# EngineersThumb.net
KiCad netlist of a schematic drawn in EAGLE
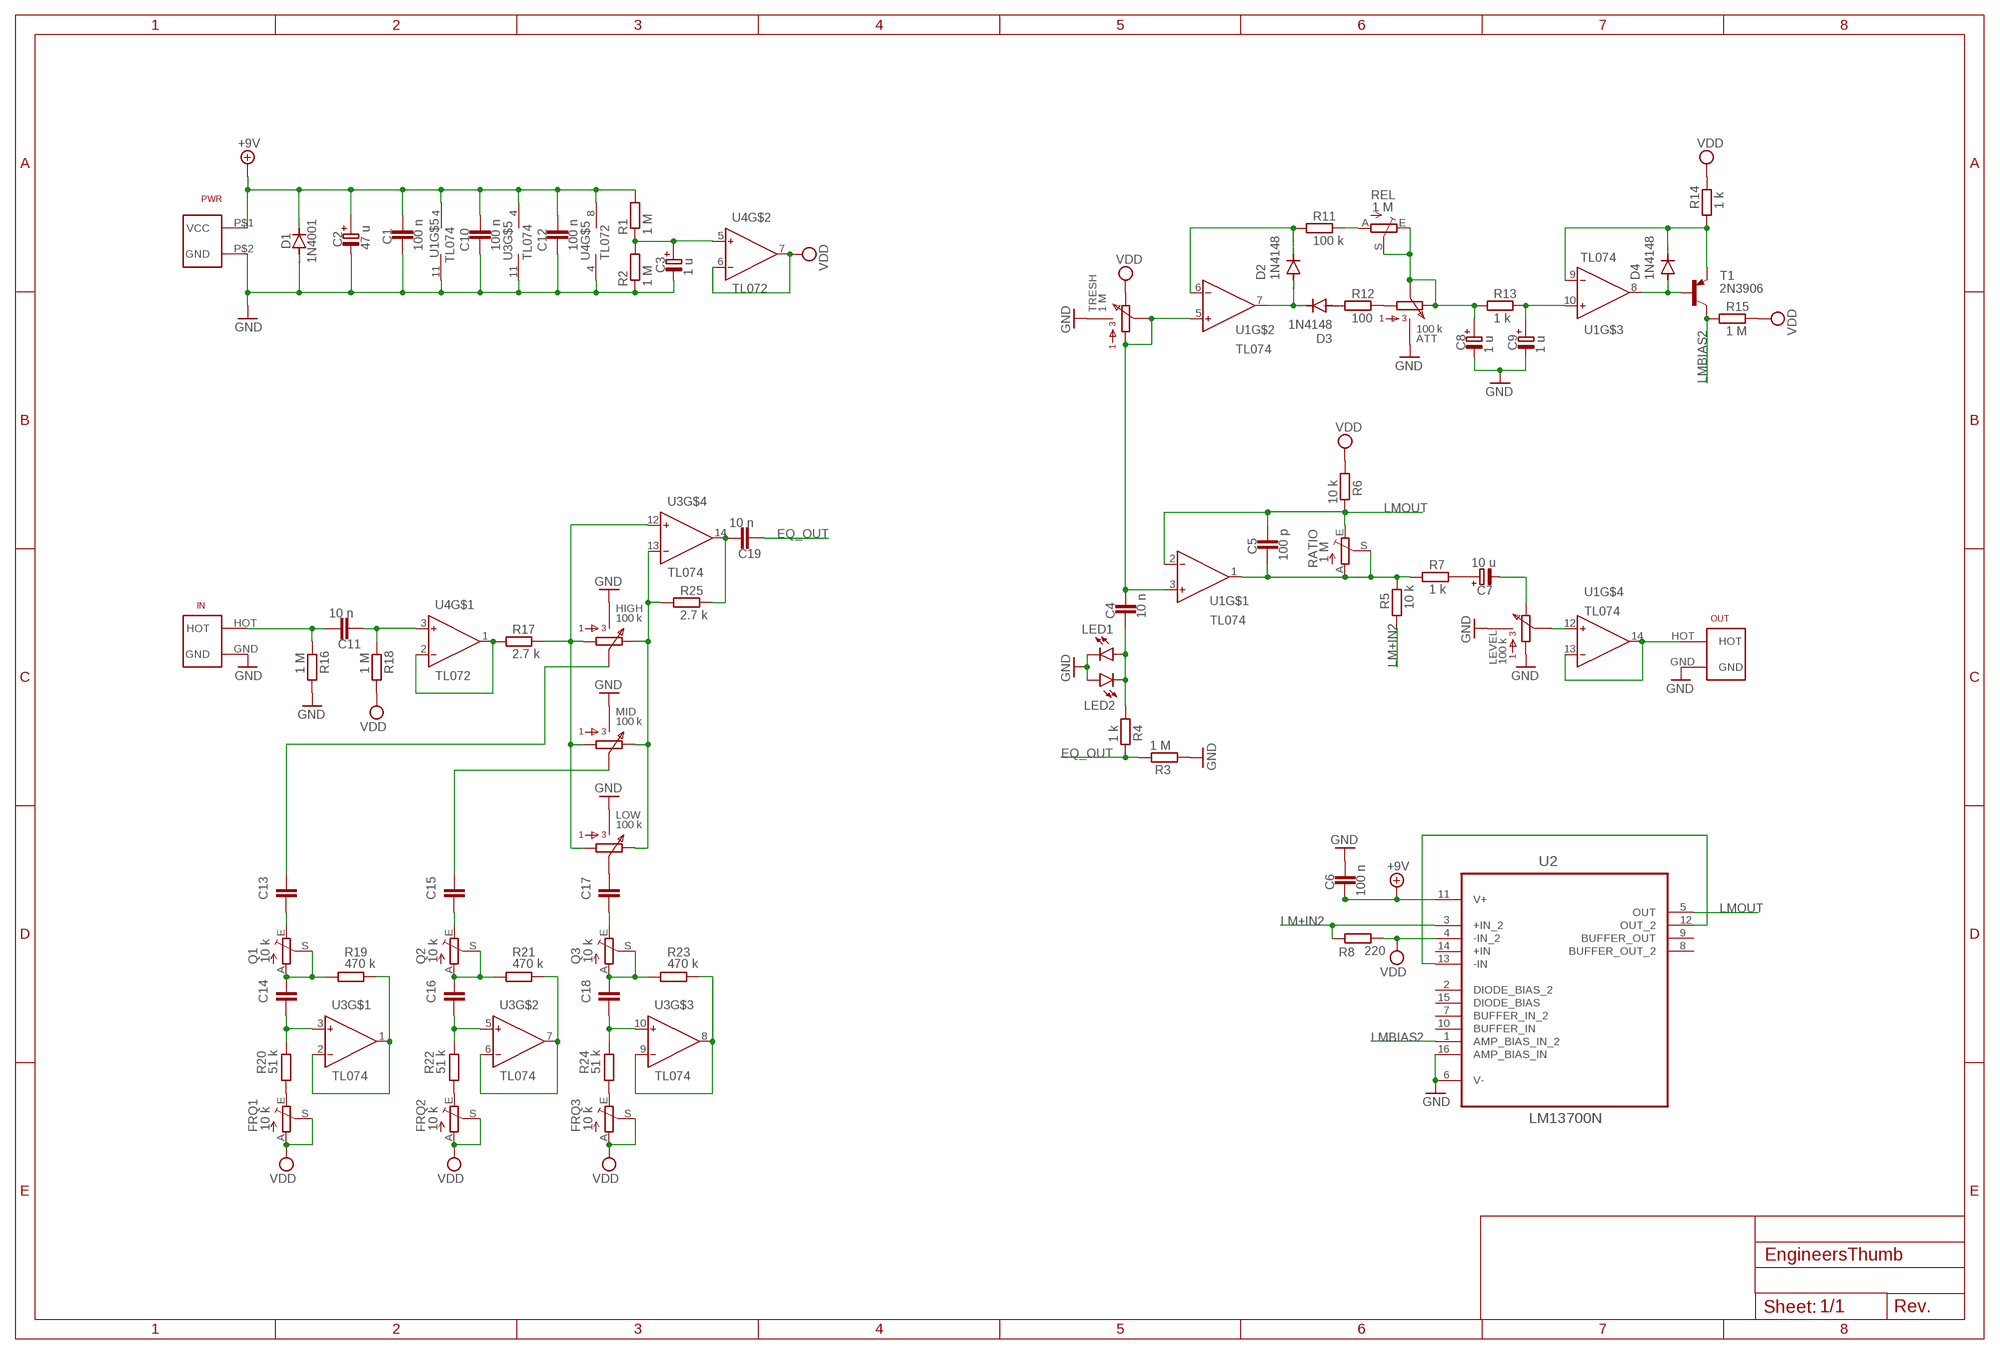
[diagram p0: schematic, sheet 1]

(export (version "E")
  (design (tool "Eeschema 10.0.6"))
  (components
    (comp (ref "ATT")
      (value "100 k")
      (footprint "eagle-import:RK09L1140")
      (libsource (lib "eagle-import") (part "RK09L1140"))
    )
    (comp (ref "C1")
      (value "100 n")
      (footprint "eagle-import:C025-025X050")
      (libsource (lib "eagle-import") (part "C-EU025-025X050"))
    )
    (comp (ref "C2")
      (value "47 u")
      (footprint "eagle-import:E2,0-5")
      (libsource (lib "eagle-import") (part "C-PR-2,0X5"))
    )
    (comp (ref "C3")
      (value "1 u")
      (footprint "eagle-import:E2,0-5")
      (libsource (lib "eagle-import") (part "C-PR-2,0X5"))
    )
    (comp (ref "C4")
      (value "10 n")
      (footprint "eagle-import:C025-025X050")
      (libsource (lib "eagle-import") (part "C-EU025-025X050"))
    )
    (comp (ref "C5")
      (value "100 p")
      (footprint "eagle-import:C025-025X050")
      (libsource (lib "eagle-import") (part "C-EU025-025X050"))
    )
    (comp (ref "C6")
      (value "100 n")
      (footprint "eagle-import:C025-025X050")
      (libsource (lib "eagle-import") (part "C-EU025-025X050"))
    )
    (comp (ref "C7")
      (value "10 u")
      (footprint "eagle-import:E2,0-5")
      (libsource (lib "eagle-import") (part "C-PR-2,0X5"))
    )
    (comp (ref "C8")
      (value "1 u")
      (footprint "eagle-import:E2,0-5")
      (libsource (lib "eagle-import") (part "C-PR-2,0X5"))
    )
    (comp (ref "C9")
      (value "1 u")
      (footprint "eagle-import:E2,0-5")
      (libsource (lib "eagle-import") (part "C-PR-2,0X5"))
    )
    (comp (ref "C10")
      (value "100 n")
      (footprint "eagle-import:C025-025X050")
      (libsource (lib "eagle-import") (part "C-EU025-025X050"))
    )
    (comp (ref "C11")
      (value "10 n")
      (footprint "eagle-import:C025-025X050")
      (libsource (lib "eagle-import") (part "C-EU025-025X050"))
    )
    (comp (ref "C12")
      (value "100 n")
      (footprint "eagle-import:C025-025X050")
      (libsource (lib "eagle-import") (part "C-EU025-025X050"))
    )
    (comp (ref "C13")
      (value "C-EU025-025X050")
      (footprint "eagle-import:C025-025X050")
      (libsource (lib "eagle-import") (part "C-EU025-025X050"))
    )
    (comp (ref "C14")
      (value "C-EU025-025X050")
      (footprint "eagle-import:C025-025X050")
      (libsource (lib "eagle-import") (part "C-EU025-025X050"))
    )
    (comp (ref "C15")
      (value "C-EU025-025X050")
      (footprint "eagle-import:C025-025X050")
      (libsource (lib "eagle-import") (part "C-EU025-025X050"))
    )
    (comp (ref "C16")
      (value "C-EU025-025X050")
      (footprint "eagle-import:C025-025X050")
      (libsource (lib "eagle-import") (part "C-EU025-025X050"))
    )
    (comp (ref "C17")
      (value "C-EU025-025X050")
      (footprint "eagle-import:C025-025X050")
      (libsource (lib "eagle-import") (part "C-EU025-025X050"))
    )
    (comp (ref "C18")
      (value "C-EU025-025X050")
      (footprint "eagle-import:C025-025X050")
      (libsource (lib "eagle-import") (part "C-EU025-025X050"))
    )
    (comp (ref "C19")
      (value "10 n")
      (footprint "eagle-import:C025-025X050")
      (libsource (lib "eagle-import") (part "C-EU025-025X050"))
    )
    (comp (ref "D1")
      (value "1N4001")
      (footprint "eagle-import:DO41-10")
      (libsource (lib "eagle-import") (part "1N4004"))
    )
    (comp (ref "D2")
      (value "1N4148")
      (footprint "eagle-import:DO35-10")
      (libsource (lib "eagle-import") (part "1N4148DO35-10"))
    )
    (comp (ref "D3")
      (value "1N4148")
      (footprint "eagle-import:DO35-10")
      (libsource (lib "eagle-import") (part "1N4148DO35-10"))
    )
    (comp (ref "D4")
      (value "1N4148")
      (footprint "eagle-import:DO35-10")
      (libsource (lib "eagle-import") (part "1N4148DO35-10"))
    )
    (comp (ref "FRQ1")
      (value "10 k")
      (footprint "eagle-import:B64Y")
      (libsource (lib "eagle-import") (part "TRIM_EU-B64Y"))
    )
    (comp (ref "FRQ2")
      (value "10 k")
      (footprint "eagle-import:B64Y")
      (libsource (lib "eagle-import") (part "TRIM_EU-B64Y"))
    )
    (comp (ref "FRQ3")
      (value "10 k")
      (footprint "eagle-import:B64Y")
      (libsource (lib "eagle-import") (part "TRIM_EU-B64Y"))
    )
    (comp (ref "HIGH")
      (value "100 k")
      (footprint "eagle-import:RK09L1140")
      (libsource (lib "eagle-import") (part "RK09L1140"))
    )
    (comp (ref "IN")
      (value "UNBALANCED_INPUT_JACK")
      (footprint "eagle-import:BALANCED_INPUT_JACK")
      (libsource (lib "eagle-import") (part "UNBALANCED_INPUT_JACK"))
    )
    (comp (ref "LED1")
      (value "TLLG4400")
      (footprint "eagle-import:LED3MM")
      (fields (field (name "MF") "VISHAY SEMICONDUCTOR"))
      (libsource (lib "eagle-import") (part "TLLG4400"))
    )
    (comp (ref "LED2")
      (value "TLLG4400")
      (footprint "eagle-import:LED3MM")
      (fields (field (name "MF") "VISHAY SEMICONDUCTOR"))
      (libsource (lib "eagle-import") (part "TLLG4400"))
    )
    (comp (ref "LEVEL")
      (value "100 k")
      (footprint "eagle-import:RK09L1140")
      (libsource (lib "eagle-import") (part "RK09L1140"))
    )
    (comp (ref "LOW")
      (value "100 k")
      (footprint "eagle-import:RK09L1140")
      (libsource (lib "eagle-import") (part "RK09L1140"))
    )
    (comp (ref "MID")
      (value "100 k")
      (footprint "eagle-import:RK09L1140")
      (libsource (lib "eagle-import") (part "RK09L1140"))
    )
    (comp (ref "OUT")
      (value "UNBALANCED_INPUT_JACK")
      (footprint "eagle-import:BALANCED_INPUT_JACK")
      (libsource (lib "eagle-import") (part "UNBALANCED_INPUT_JACK"))
    )
    (comp (ref "PWR")
      (value "PWR")
      (footprint "eagle-import:PWR")
      (libsource (lib "eagle-import") (part "PWR"))
    )
    (comp (ref "Q1")
      (value "10 k")
      (footprint "eagle-import:B64Y")
      (libsource (lib "eagle-import") (part "TRIM_EU-B64Y"))
    )
    (comp (ref "Q2")
      (value "10 k")
      (footprint "eagle-import:B64Y")
      (libsource (lib "eagle-import") (part "TRIM_EU-B64Y"))
    )
    (comp (ref "Q3")
      (value "10 k")
      (footprint "eagle-import:B64Y")
      (libsource (lib "eagle-import") (part "TRIM_EU-B64Y"))
    )
    (comp (ref "R1")
      (value "1 M")
      (footprint "eagle-import:0204_7")
      (libsource (lib "eagle-import") (part "R-EU_0204/7"))
    )
    (comp (ref "R2")
      (value "1 M")
      (footprint "eagle-import:0204_7")
      (libsource (lib "eagle-import") (part "R-EU_0204/7"))
    )
    (comp (ref "R3")
      (value "1 M")
      (footprint "eagle-import:0204_7")
      (libsource (lib "eagle-import") (part "R-EU_0204/7"))
    )
    (comp (ref "R4")
      (value "1 k")
      (footprint "eagle-import:0204_7")
      (libsource (lib "eagle-import") (part "R-EU_0204/7"))
    )
    (comp (ref "R5")
      (value "10 k")
      (footprint "eagle-import:0204_7")
      (libsource (lib "eagle-import") (part "R-EU_0204/7"))
    )
    (comp (ref "R6")
      (value "10 k")
      (footprint "eagle-import:0204_7")
      (libsource (lib "eagle-import") (part "R-EU_0204/7"))
    )
    (comp (ref "R7")
      (value "1 k")
      (footprint "eagle-import:0204_7")
      (libsource (lib "eagle-import") (part "R-EU_0204/7"))
    )
    (comp (ref "R8")
      (value "220")
      (footprint "eagle-import:0204_7")
      (libsource (lib "eagle-import") (part "R-EU_0204/7"))
    )
    (comp (ref "R11")
      (value "100 k")
      (footprint "eagle-import:0204_7")
      (libsource (lib "eagle-import") (part "R-EU_0204/7"))
    )
    (comp (ref "R12")
      (value "100")
      (footprint "eagle-import:0204_7")
      (libsource (lib "eagle-import") (part "R-EU_0204/7"))
    )
    (comp (ref "R13")
      (value "1 k")
      (footprint "eagle-import:0204_7")
      (libsource (lib "eagle-import") (part "R-EU_0204/7"))
    )
    (comp (ref "R14")
      (value "1 k")
      (footprint "eagle-import:0204_7")
      (libsource (lib "eagle-import") (part "R-EU_0204/7"))
    )
    (comp (ref "R15")
      (value "1 M")
      (footprint "eagle-import:0204_7")
      (libsource (lib "eagle-import") (part "R-EU_0204/7"))
    )
    (comp (ref "R16")
      (value "1 M")
      (footprint "eagle-import:0204_7")
      (libsource (lib "eagle-import") (part "R-EU_0204/7"))
    )
    (comp (ref "R17")
      (value "2.7 k")
      (footprint "eagle-import:0204_7")
      (libsource (lib "eagle-import") (part "R-EU_0204/7"))
    )
    (comp (ref "R18")
      (value "1 M")
      (footprint "eagle-import:0204_7")
      (libsource (lib "eagle-import") (part "R-EU_0204/7"))
    )
    (comp (ref "R19")
      (value "470 k")
      (footprint "eagle-import:0204_7")
      (libsource (lib "eagle-import") (part "R-EU_0204/7"))
    )
    (comp (ref "R20")
      (value "51 k")
      (footprint "eagle-import:0204_7")
      (libsource (lib "eagle-import") (part "R-EU_0204/7"))
    )
    (comp (ref "R21")
      (value "470 k")
      (footprint "eagle-import:0204_7")
      (libsource (lib "eagle-import") (part "R-EU_0204/7"))
    )
    (comp (ref "R22")
      (value "51 k")
      (footprint "eagle-import:0204_7")
      (libsource (lib "eagle-import") (part "R-EU_0204/7"))
    )
    (comp (ref "R23")
      (value "470 k")
      (footprint "eagle-import:0204_7")
      (libsource (lib "eagle-import") (part "R-EU_0204/7"))
    )
    (comp (ref "R24")
      (value "51 k")
      (footprint "eagle-import:0204_7")
      (libsource (lib "eagle-import") (part "R-EU_0204/7"))
    )
    (comp (ref "R25")
      (value "2.7 k")
      (footprint "eagle-import:0204_7")
      (libsource (lib "eagle-import") (part "R-EU_0204/7"))
    )
    (comp (ref "RATIO")
      (value "1 M")
      (footprint "eagle-import:B64Y")
      (libsource (lib "eagle-import") (part "TRIM_EU-B64Y"))
    )
    (comp (ref "REL")
      (value "1 M")
      (footprint "eagle-import:B64Y")
      (libsource (lib "eagle-import") (part "TRIM_EU-B64Y"))
    )
    (comp (ref "T1")
      (value "2N3906")
      (footprint "eagle-import:TO92")
      (libsource (lib "eagle-import") (part "2N3906"))
    )
    (comp (ref "TRESH")
      (value "1 M")
      (footprint "eagle-import:RK09L1140")
      (libsource (lib "eagle-import") (part "RK09L1140"))
    )
    (comp (ref "U1")
      (value "TL074")
      (footprint "eagle-import:DIP762W53P254L1969H508Q14B")
      (fields (field (name "MPN") "TL074CN"))
      (libsource (lib "eagle-import") (part "TL074IDTPDIP-14"))
    )
    (comp (ref "U2")
      (value "LM13700N")
      (footprint "eagle-import:DIP254P762X508-16")
      (fields (field (name "MPN") "LM13700N/NOPB"))
      (libsource (lib "eagle-import") (part "LM13700N"))
    )
    (comp (ref "U3")
      (value "TL074")
      (footprint "eagle-import:DIP762W53P254L1969H508Q14B")
      (fields (field (name "MPN") "TL074CN"))
      (libsource (lib "eagle-import") (part "TL074IDTPDIP-14"))
    )
    (comp (ref "U4")
      (value "TL072")
      (footprint "eagle-import:DIP762W53P254L980H508Q8B")
      (fields (field (name "MPN") "TL072IP"))
      (libsource (lib "eagle-import") (part "TL072PDIP-8"))
    )
  )
  (nets
    (net (code "1") (name "+9V") (class "Default")
      (node (ref "C1") (pin "1") (pinfunction "1_1") (pintype "passive"))
      (node (ref "C10") (pin "1") (pinfunction "1_1") (pintype "passive"))
      (node (ref "C12") (pin "1") (pinfunction "1_1") (pintype "passive"))
      (node (ref "C2") (pin "+") (pinfunction "+_+") (pintype "passive"))
      (node (ref "C6") (pin "2") (pinfunction "2_2") (pintype "passive"))
      (node (ref "D1") (pin "C") (pinfunction "C_C") (pintype "passive"))
      (node (ref "PWR") (pin "P$1") (pinfunction "VCC_P$1") (pintype "bidirectional"))
      (node (ref "R1") (pin "2") (pinfunction "2_2") (pintype "passive"))
      (node (ref "U1") (pin "4") (pinfunction "V+_4") (pintype "power_in"))
      (node (ref "U2") (pin "11") (pinfunction "V+_11") (pintype "power_in"))
      (node (ref "U3") (pin "4") (pinfunction "V+_4") (pintype "power_in"))
      (node (ref "U4") (pin "8") (pinfunction "V+_8") (pintype "power_in"))
    )
    (net (code "2") (name "/EQ_OUT") (class "Default")
      (node (ref "C19") (pin "2") (pinfunction "2_2") (pintype "passive"))
      (node (ref "R3") (pin "2") (pinfunction "2_2") (pintype "passive"))
      (node (ref "R4") (pin "2") (pinfunction "2_2") (pintype "passive"))
    )
    (net (code "3") (name "/LM+IN2") (class "Default")
      (node (ref "R5") (pin "1") (pinfunction "1_1") (pintype "passive"))
      (node (ref "R8") (pin "1") (pinfunction "1_1") (pintype "passive"))
      (node (ref "U2") (pin "3") (pinfunction "+IN_2_3") (pintype "input"))
    )
    (net (code "4") (name "/LMBIAS2") (class "Default")
      (node (ref "R15") (pin "1") (pinfunction "1_1") (pintype "passive"))
      (node (ref "T1") (pin "1") (pinfunction "C_1") (pintype "passive"))
      (node (ref "U2") (pin "1") (pinfunction "AMP_BIAS_IN_2_1") (pintype "input"))
    )
    (net (code "5") (name "/LMOUT") (class "Default")
      (node (ref "C5") (pin "1") (pinfunction "1_1") (pintype "passive"))
      (node (ref "R6") (pin "2") (pinfunction "2_2") (pintype "passive"))
      (node (ref "RATIO") (pin "E") (pinfunction "E_E") (pintype "passive"))
      (node (ref "U1") (pin "2") (pinfunction "IN-_2") (pintype "input"))
      (node (ref "U2") (pin "5") (pinfunction "OUT_5") (pintype "output"))
    )
    (net (code "6") (name "GND") (class "Default")
      (node (ref "ATT") (pin "P$4") (pinfunction "P$1_P$4") (pintype "bidirectional"))
      (node (ref "ATT") (pin "P$5") (pinfunction "P$1_P$5") (pintype "bidirectional"))
      (node (ref "C1") (pin "2") (pinfunction "2_2") (pintype "passive"))
      (node (ref "C10") (pin "2") (pinfunction "2_2") (pintype "passive"))
      (node (ref "C12") (pin "2") (pinfunction "2_2") (pintype "passive"))
      (node (ref "C2") (pin "-") (pinfunction "-_-") (pintype "passive"))
      (node (ref "C3") (pin "-") (pinfunction "-_-") (pintype "passive"))
      (node (ref "C6") (pin "1") (pinfunction "1_1") (pintype "passive"))
      (node (ref "C8") (pin "-") (pinfunction "-_-") (pintype "passive"))
      (node (ref "C9") (pin "-") (pinfunction "-_-") (pintype "passive"))
      (node (ref "D1") (pin "A") (pinfunction "A_A") (pintype "passive"))
      (node (ref "HIGH") (pin "P$4") (pinfunction "P$1_P$4") (pintype "bidirectional"))
      (node (ref "HIGH") (pin "P$5") (pinfunction "P$1_P$5") (pintype "bidirectional"))
      (node (ref "IN") (pin "GND") (pinfunction "GND_GND") (pintype "bidirectional"))
      (node (ref "LED1") (pin "K") (pinfunction "C_K") (pintype "passive"))
      (node (ref "LED2") (pin "A") (pinfunction "A_A") (pintype "passive"))
      (node (ref "LEVEL") (pin "P$1") (pinfunction "1_P$1") (pintype "passive"))
      (node (ref "LEVEL") (pin "P$4") (pinfunction "P$1_P$4") (pintype "bidirectional"))
      (node (ref "LEVEL") (pin "P$5") (pinfunction "P$1_P$5") (pintype "bidirectional"))
      (node (ref "LOW") (pin "P$4") (pinfunction "P$1_P$4") (pintype "bidirectional"))
      (node (ref "LOW") (pin "P$5") (pinfunction "P$1_P$5") (pintype "bidirectional"))
      (node (ref "MID") (pin "P$4") (pinfunction "P$1_P$4") (pintype "bidirectional"))
      (node (ref "MID") (pin "P$5") (pinfunction "P$1_P$5") (pintype "bidirectional"))
      (node (ref "OUT") (pin "GND") (pinfunction "GND_GND") (pintype "bidirectional"))
      (node (ref "PWR") (pin "P$2") (pinfunction "GND_P$2") (pintype "bidirectional"))
      (node (ref "R16") (pin "1") (pinfunction "1_1") (pintype "passive"))
      (node (ref "R2") (pin "1") (pinfunction "1_1") (pintype "passive"))
      (node (ref "R3") (pin "1") (pinfunction "1_1") (pintype "passive"))
      (node (ref "TRESH") (pin "P$4") (pinfunction "P$1_P$4") (pintype "bidirectional"))
      (node (ref "TRESH") (pin "P$5") (pinfunction "P$1_P$5") (pintype "bidirectional"))
      (node (ref "U1") (pin "11") (pinfunction "V-_11") (pintype "power_in"))
      (node (ref "U2") (pin "16") (pinfunction "AMP_BIAS_IN_16") (pintype "input"))
      (node (ref "U2") (pin "6") (pinfunction "V-_6") (pintype "power_in"))
      (node (ref "U3") (pin "11") (pinfunction "V-_11") (pintype "power_in"))
      (node (ref "U4") (pin "4") (pinfunction "V-_4") (pintype "power_in"))
    )
    (net (code "7") (name "Net-(ATT-1)") (class "Default")
      (node (ref "ATT") (pin "P$1") (pinfunction "1_P$1") (pintype "passive"))
      (node (ref "R12") (pin "2") (pinfunction "2_2") (pintype "passive"))
    )
    (net (code "8") (name "Net-(ATT-2)") (class "Default")
      (node (ref "ATT") (pin "P$2") (pinfunction "2_P$2") (pintype "passive"))
      (node (ref "ATT") (pin "P$3") (pinfunction "3_P$3") (pintype "passive"))
      (node (ref "C8") (pin "+") (pinfunction "+_+") (pintype "passive"))
      (node (ref "R13") (pin "1") (pinfunction "1_1") (pintype "passive"))
      (node (ref "REL") (pin "E") (pinfunction "E_E") (pintype "passive"))
      (node (ref "REL") (pin "S") (pinfunction "S_S") (pintype "passive"))
    )
    (net (code "9") (name "Net-(C7-Pad+)") (class "Default")
      (node (ref "C7") (pin "+") (pinfunction "+_+") (pintype "passive"))
      (node (ref "R7") (pin "2") (pinfunction "2_2") (pintype "passive"))
    )
    (net (code "10") (name "Net-(C11-Pad1)") (class "Default")
      (node (ref "C11") (pin "1") (pinfunction "1_1") (pintype "passive"))
      (node (ref "IN") (pin "HOT") (pinfunction "HOT_HOT") (pintype "bidirectional"))
      (node (ref "R16") (pin "2") (pinfunction "2_2") (pintype "passive"))
    )
    (net (code "11") (name "Net-(C13-Pad1)") (class "Default")
      (node (ref "C13") (pin "1") (pinfunction "1_1") (pintype "passive"))
      (node (ref "Q1") (pin "E") (pinfunction "E_E") (pintype "passive"))
    )
    (net (code "12") (name "Net-(C14-Pad2)") (class "Default")
      (node (ref "C14") (pin "2") (pinfunction "2_2") (pintype "passive"))
      (node (ref "Q1") (pin "A") (pinfunction "A_A") (pintype "passive"))
      (node (ref "Q1") (pin "S") (pinfunction "S_S") (pintype "passive"))
      (node (ref "R19") (pin "1") (pinfunction "1_1") (pintype "passive"))
    )
    (net (code "13") (name "Net-(C15-Pad1)") (class "Default")
      (node (ref "C15") (pin "1") (pinfunction "1_1") (pintype "passive"))
      (node (ref "Q2") (pin "E") (pinfunction "E_E") (pintype "passive"))
    )
    (net (code "14") (name "Net-(C16-Pad2)") (class "Default")
      (node (ref "C16") (pin "2") (pinfunction "2_2") (pintype "passive"))
      (node (ref "Q2") (pin "A") (pinfunction "A_A") (pintype "passive"))
      (node (ref "Q2") (pin "S") (pinfunction "S_S") (pintype "passive"))
      (node (ref "R21") (pin "1") (pinfunction "1_1") (pintype "passive"))
    )
    (net (code "15") (name "Net-(C17-Pad1)") (class "Default")
      (node (ref "C17") (pin "1") (pinfunction "1_1") (pintype "passive"))
      (node (ref "Q3") (pin "E") (pinfunction "E_E") (pintype "passive"))
    )
    (net (code "16") (name "Net-(C18-Pad2)") (class "Default")
      (node (ref "C18") (pin "2") (pinfunction "2_2") (pintype "passive"))
      (node (ref "Q3") (pin "A") (pinfunction "A_A") (pintype "passive"))
      (node (ref "Q3") (pin "S") (pinfunction "S_S") (pintype "passive"))
      (node (ref "R23") (pin "1") (pinfunction "1_1") (pintype "passive"))
    )
    (net (code "17") (name "Net-(D3-PadA)") (class "Default")
      (node (ref "D3") (pin "A") (pinfunction "A_A") (pintype "passive"))
      (node (ref "R12") (pin "1") (pinfunction "1_1") (pintype "passive"))
    )
    (net (code "18") (name "Net-(FRQ1-PadE)") (class "Default")
      (node (ref "FRQ1") (pin "E") (pinfunction "E_E") (pintype "passive"))
      (node (ref "R20") (pin "1") (pinfunction "1_1") (pintype "passive"))
    )
    (net (code "19") (name "Net-(FRQ2-PadE)") (class "Default")
      (node (ref "FRQ2") (pin "E") (pinfunction "E_E") (pintype "passive"))
      (node (ref "R22") (pin "1") (pinfunction "1_1") (pintype "passive"))
    )
    (net (code "20") (name "Net-(FRQ3-PadE)") (class "Default")
      (node (ref "FRQ3") (pin "E") (pinfunction "E_E") (pintype "passive"))
      (node (ref "R24") (pin "1") (pinfunction "1_1") (pintype "passive"))
    )
    (net (code "21") (name "Net-(HIGH-1)") (class "Default")
      (node (ref "HIGH") (pin "P$1") (pinfunction "1_P$1") (pintype "passive"))
      (node (ref "LOW") (pin "P$1") (pinfunction "1_P$1") (pintype "passive"))
      (node (ref "MID") (pin "P$1") (pinfunction "1_P$1") (pintype "passive"))
      (node (ref "R17") (pin "2") (pinfunction "2_2") (pintype "passive"))
      (node (ref "U3") (pin "12") (pinfunction "IN+_12") (pintype "input"))
    )
    (net (code "22") (name "Net-(HIGH-2)") (class "Default")
      (node (ref "C13") (pin "2") (pinfunction "2_2") (pintype "passive"))
      (node (ref "HIGH") (pin "P$2") (pinfunction "2_P$2") (pintype "passive"))
    )
    (net (code "23") (name "Net-(HIGH-3)") (class "Default")
      (node (ref "HIGH") (pin "P$3") (pinfunction "3_P$3") (pintype "passive"))
      (node (ref "LOW") (pin "P$3") (pinfunction "3_P$3") (pintype "passive"))
      (node (ref "MID") (pin "P$3") (pinfunction "3_P$3") (pintype "passive"))
      (node (ref "R25") (pin "1") (pinfunction "1_1") (pintype "passive"))
      (node (ref "U3") (pin "13") (pinfunction "IN-_13") (pintype "input"))
    )
    (net (code "24") (name "Net-(LED2-C)") (class "Default")
      (node (ref "C4") (pin "2") (pinfunction "2_2") (pintype "passive"))
      (node (ref "LED1") (pin "A") (pinfunction "A_A") (pintype "passive"))
      (node (ref "LED2") (pin "K") (pinfunction "C_K") (pintype "passive"))
      (node (ref "R4") (pin "1") (pinfunction "1_1") (pintype "passive"))
    )
    (net (code "25") (name "Net-(LEVEL-2)") (class "Default")
      (node (ref "LEVEL") (pin "P$2") (pinfunction "2_P$2") (pintype "passive"))
      (node (ref "U1") (pin "12") (pinfunction "IN+_12") (pintype "input"))
    )
    (net (code "26") (name "Net-(LEVEL-3)") (class "Default")
      (node (ref "C7") (pin "-") (pinfunction "-_-") (pintype "passive"))
      (node (ref "LEVEL") (pin "P$3") (pinfunction "3_P$3") (pintype "passive"))
    )
    (net (code "27") (name "Net-(LOW-2)") (class "Default")
      (node (ref "C17") (pin "2") (pinfunction "2_2") (pintype "passive"))
      (node (ref "LOW") (pin "P$2") (pinfunction "2_P$2") (pintype "passive"))
    )
    (net (code "28") (name "Net-(MID-2)") (class "Default")
      (node (ref "C15") (pin "2") (pinfunction "2_2") (pintype "passive"))
      (node (ref "MID") (pin "P$2") (pinfunction "2_P$2") (pintype "passive"))
    )
    (net (code "29") (name "Net-(R11-Pad2)") (class "Default")
      (node (ref "R11") (pin "2") (pinfunction "2_2") (pintype "passive"))
      (node (ref "REL") (pin "A") (pinfunction "A_A") (pintype "passive"))
    )
    (net (code "30") (name "Net-(T1-B)") (class "Default")
      (node (ref "D4") (pin "A") (pinfunction "A_A") (pintype "passive"))
      (node (ref "T1") (pin "2") (pinfunction "B_2") (pintype "passive"))
      (node (ref "U1") (pin "8") (pinfunction "OUT_8") (pintype "output"))
    )
    (net (code "31") (name "Net-(T1-E)") (class "Default")
      (node (ref "D4") (pin "C") (pinfunction "C_C") (pintype "passive"))
      (node (ref "R14") (pin "1") (pinfunction "1_1") (pintype "passive"))
      (node (ref "T1") (pin "3") (pinfunction "E_3") (pintype "passive"))
      (node (ref "U1") (pin "9") (pinfunction "IN-_9") (pintype "input"))
    )
    (net (code "32") (name "Net-(TRESH-1)") (class "Default")
      (node (ref "C4") (pin "1") (pinfunction "1_1") (pintype "passive"))
      (node (ref "TRESH") (pin "P$1") (pinfunction "1_P$1") (pintype "passive"))
      (node (ref "TRESH") (pin "P$2") (pinfunction "2_P$2") (pintype "passive"))
      (node (ref "U1") (pin "3") (pinfunction "IN+_3") (pintype "input"))
      (node (ref "U1") (pin "5") (pinfunction "IN+_5") (pintype "input"))
    )
    (net (code "33") (name "Net-(U1A-OUT)") (class "Default")
      (node (ref "C5") (pin "2") (pinfunction "2_2") (pintype "passive"))
      (node (ref "R5") (pin "2") (pinfunction "2_2") (pintype "passive"))
      (node (ref "R7") (pin "1") (pinfunction "1_1") (pintype "passive"))
      (node (ref "RATIO") (pin "A") (pinfunction "A_A") (pintype "passive"))
      (node (ref "RATIO") (pin "S") (pinfunction "S_S") (pintype "passive"))
      (node (ref "U1") (pin "1") (pinfunction "OUT_1") (pintype "output"))
    )
    (net (code "34") (name "Net-(U1B-IN-)") (class "Default")
      (node (ref "D2") (pin "C") (pinfunction "C_C") (pintype "passive"))
      (node (ref "R11") (pin "1") (pinfunction "1_1") (pintype "passive"))
      (node (ref "U1") (pin "6") (pinfunction "IN-_6") (pintype "input"))
    )
    (net (code "35") (name "Net-(U1B-OUT)") (class "Default")
      (node (ref "D2") (pin "A") (pinfunction "A_A") (pintype "passive"))
      (node (ref "D3") (pin "C") (pinfunction "C_C") (pintype "passive"))
      (node (ref "U1") (pin "7") (pinfunction "OUT_7") (pintype "output"))
    )
    (net (code "36") (name "Net-(U1C-IN+)") (class "Default")
      (node (ref "C9") (pin "+") (pinfunction "+_+") (pintype "passive"))
      (node (ref "R13") (pin "2") (pinfunction "2_2") (pintype "passive"))
      (node (ref "U1") (pin "10") (pinfunction "IN+_10") (pintype "input"))
    )
    (net (code "37") (name "Net-(U1D-IN-)") (class "Default")
      (node (ref "OUT") (pin "HOT") (pinfunction "HOT_HOT") (pintype "bidirectional"))
      (node (ref "U1") (pin "13") (pinfunction "IN-_13") (pintype "input"))
      (node (ref "U1") (pin "14") (pinfunction "OUT_14") (pintype "output"))
    )
    (net (code "38") (name "Net-(U2--IN)") (class "Default")
      (node (ref "U2") (pin "12") (pinfunction "OUT_2_12") (pintype "output"))
      (node (ref "U2") (pin "13") (pinfunction "-IN_13") (pintype "input"))
    )
    (net (code "39") (name "Net-(U3A-IN+)") (class "Default")
      (node (ref "C14") (pin "1") (pinfunction "1_1") (pintype "passive"))
      (node (ref "R20") (pin "2") (pinfunction "2_2") (pintype "passive"))
      (node (ref "U3") (pin "3") (pinfunction "IN+_3") (pintype "input"))
    )
    (net (code "40") (name "Net-(U3A-IN-)") (class "Default")
      (node (ref "R19") (pin "2") (pinfunction "2_2") (pintype "passive"))
      (node (ref "U3") (pin "1") (pinfunction "OUT_1") (pintype "output"))
      (node (ref "U3") (pin "2") (pinfunction "IN-_2") (pintype "input"))
    )
    (net (code "41") (name "Net-(U3B-IN+)") (class "Default")
      (node (ref "C16") (pin "1") (pinfunction "1_1") (pintype "passive"))
      (node (ref "R22") (pin "2") (pinfunction "2_2") (pintype "passive"))
      (node (ref "U3") (pin "5") (pinfunction "IN+_5") (pintype "input"))
    )
    (net (code "42") (name "Net-(U3B-IN-)") (class "Default")
      (node (ref "R21") (pin "2") (pinfunction "2_2") (pintype "passive"))
      (node (ref "U3") (pin "6") (pinfunction "IN-_6") (pintype "input"))
      (node (ref "U3") (pin "7") (pinfunction "OUT_7") (pintype "output"))
    )
    (net (code "43") (name "Net-(U3C-IN+)") (class "Default")
      (node (ref "C18") (pin "1") (pinfunction "1_1") (pintype "passive"))
      (node (ref "R24") (pin "2") (pinfunction "2_2") (pintype "passive"))
      (node (ref "U3") (pin "10") (pinfunction "IN+_10") (pintype "input"))
    )
    (net (code "44") (name "Net-(U3C-IN-)") (class "Default")
      (node (ref "R23") (pin "2") (pinfunction "2_2") (pintype "passive"))
      (node (ref "U3") (pin "8") (pinfunction "OUT_8") (pintype "output"))
      (node (ref "U3") (pin "9") (pinfunction "IN-_9") (pintype "input"))
    )
    (net (code "45") (name "Net-(U3D-OUT)") (class "Default")
      (node (ref "C19") (pin "1") (pinfunction "1_1") (pintype "passive"))
      (node (ref "R25") (pin "2") (pinfunction "2_2") (pintype "passive"))
      (node (ref "U3") (pin "14") (pinfunction "OUT_14") (pintype "output"))
    )
    (net (code "46") (name "Net-(U4A-IN+)") (class "Default")
      (node (ref "C11") (pin "2") (pinfunction "2_2") (pintype "passive"))
      (node (ref "R18") (pin "2") (pinfunction "2_2") (pintype "passive"))
      (node (ref "U4") (pin "3") (pinfunction "IN+_3") (pintype "input"))
    )
    (net (code "47") (name "Net-(U4A-IN-)") (class "Default")
      (node (ref "R17") (pin "1") (pinfunction "1_1") (pintype "passive"))
      (node (ref "U4") (pin "1") (pinfunction "OUT_1") (pintype "output"))
      (node (ref "U4") (pin "2") (pinfunction "IN-_2") (pintype "input"))
    )
    (net (code "48") (name "Net-(U4B-IN+)") (class "Default")
      (node (ref "C3") (pin "+") (pinfunction "+_+") (pintype "passive"))
      (node (ref "R1") (pin "1") (pinfunction "1_1") (pintype "passive"))
      (node (ref "R2") (pin "2") (pinfunction "2_2") (pintype "passive"))
      (node (ref "U4") (pin "5") (pinfunction "IN+_5") (pintype "input"))
    )
    (net (code "49") (name "VDD") (class "Default")
      (node (ref "FRQ1") (pin "A") (pinfunction "A_A") (pintype "passive"))
      (node (ref "FRQ1") (pin "S") (pinfunction "S_S") (pintype "passive"))
      (node (ref "FRQ2") (pin "A") (pinfunction "A_A") (pintype "passive"))
      (node (ref "FRQ2") (pin "S") (pinfunction "S_S") (pintype "passive"))
      (node (ref "FRQ3") (pin "A") (pinfunction "A_A") (pintype "passive"))
      (node (ref "FRQ3") (pin "S") (pinfunction "S_S") (pintype "passive"))
      (node (ref "R14") (pin "2") (pinfunction "2_2") (pintype "passive"))
      (node (ref "R15") (pin "2") (pinfunction "2_2") (pintype "passive"))
      (node (ref "R18") (pin "1") (pinfunction "1_1") (pintype "passive"))
      (node (ref "R6") (pin "1") (pinfunction "1_1") (pintype "passive"))
      (node (ref "R8") (pin "2") (pinfunction "2_2") (pintype "passive"))
      (node (ref "TRESH") (pin "P$3") (pinfunction "3_P$3") (pintype "passive"))
      (node (ref "U2") (pin "4") (pinfunction "-IN_2_4") (pintype "input"))
      (node (ref "U4") (pin "6") (pinfunction "IN-_6") (pintype "input"))
      (node (ref "U4") (pin "7") (pinfunction "OUT_7") (pintype "output"))
    )
    (net (code "50") (name "unconnected-(U2-+IN-Pad14)") (class "Default")
      (node (ref "U2") (pin "14") (pinfunction "+IN_14") (pintype "input"))
    )
    (net (code "51") (name "unconnected-(U2-BUFFER_IN-Pad10)") (class "Default")
      (node (ref "U2") (pin "10") (pinfunction "BUFFER_IN_10") (pintype "input"))
    )
    (net (code "52") (name "unconnected-(U2-BUFFER_IN_2-Pad7)") (class "Default")
      (node (ref "U2") (pin "7") (pinfunction "BUFFER_IN_2_7") (pintype "input"))
    )
    (net (code "53") (name "unconnected-(U2-BUFFER_OUT-Pad9)") (class "Default")
      (node (ref "U2") (pin "9") (pinfunction "BUFFER_OUT_9") (pintype "output"))
    )
    (net (code "54") (name "unconnected-(U2-BUFFER_OUT_2-Pad8)") (class "Default")
      (node (ref "U2") (pin "8") (pinfunction "BUFFER_OUT_2_8") (pintype "output"))
    )
    (net (code "55") (name "unconnected-(U2-DIODE_BIAS-Pad15)") (class "Default")
      (node (ref "U2") (pin "15") (pinfunction "DIODE_BIAS_15") (pintype "input"))
    )
    (net (code "56") (name "unconnected-(U2-DIODE_BIAS_2-Pad2)") (class "Default")
      (node (ref "U2") (pin "2") (pinfunction "DIODE_BIAS_2_2") (pintype "input"))
    )
  )
)
